# EtherNet.net
KiCad netlist of a schematic drawn in Altium Designer
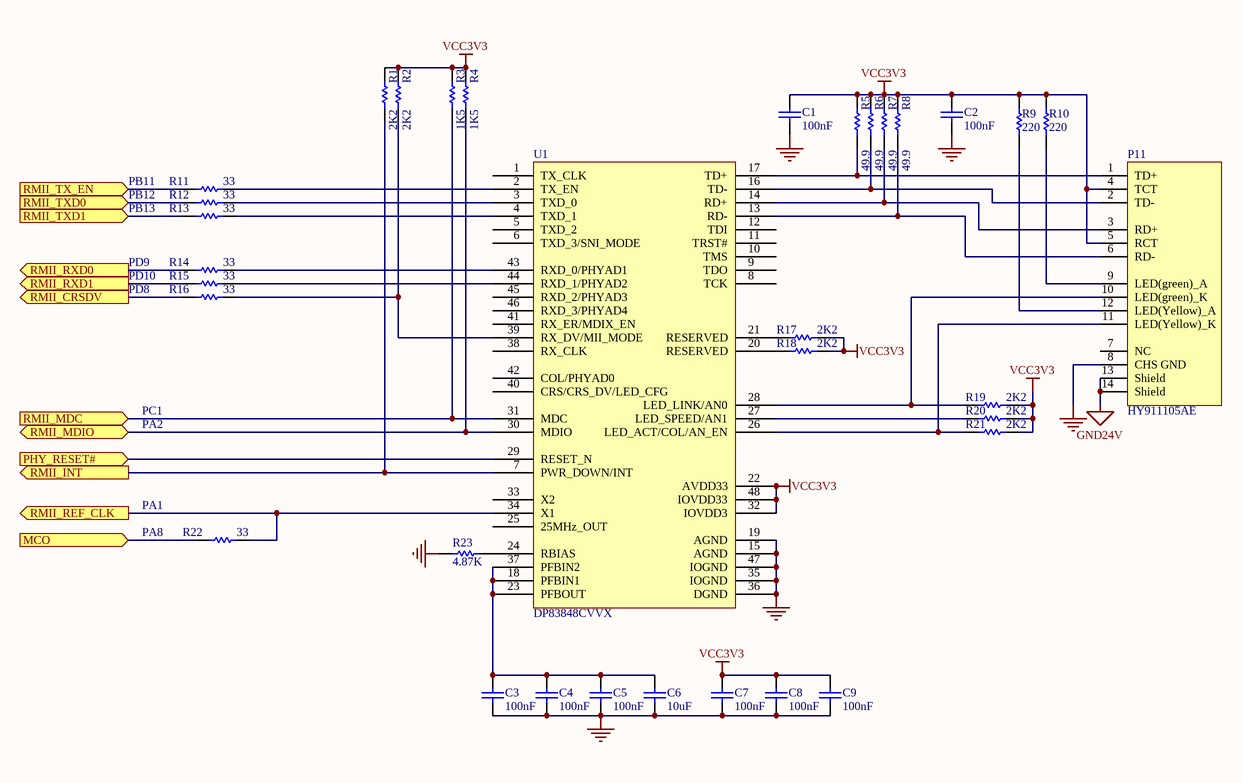
[diagram p0: EtherNet.SchDoc]

(export (version "E")
  (design (tool "Eeschema 10.0.6"))
  (components
    (comp (ref "C1")
      (value "100nF")
      (footprint "0805_C")
      (description "贴片电容")
      (libsource (lib "Miscellaneous Devices LC") (part "0805 100nF(104) 10% 50V"))
    )
    (comp (ref "C2")
      (value "100nF")
      (footprint "0805_C")
      (description "贴片电容")
      (libsource (lib "Miscellaneous Devices LC") (part "0805 100nF(104) 10% 50V"))
    )
    (comp (ref "C3")
      (value "100nF")
      (footprint "0805_C")
      (description "贴片电容")
      (libsource (lib "Miscellaneous Devices LC") (part "0805 100nF(104) 10% 50V"))
    )
    (comp (ref "C4")
      (value "100nF")
      (footprint "0805_C")
      (description "贴片电容")
      (libsource (lib "Miscellaneous Devices LC") (part "0805 100nF(104) 10% 50V"))
    )
    (comp (ref "C5")
      (value "100nF")
      (footprint "0805_C")
      (description "贴片电容")
      (libsource (lib "Miscellaneous Devices LC") (part "0805 100nF(104) 10% 50V"))
    )
    (comp (ref "C6")
      (value "10uF")
      (footprint "0805_C")
      (description "贴片电容")
      (libsource (lib "Miscellaneous Devices LC") (part "0805 10uF (106) 10% 25V"))
    )
    (comp (ref "C7")
      (value "100nF")
      (footprint "0805_C")
      (description "贴片电容")
      (libsource (lib "Miscellaneous Devices LC") (part "0805 100nF(104) 10% 50V"))
    )
    (comp (ref "C8")
      (value "100nF")
      (footprint "0805_C")
      (description "贴片电容")
      (libsource (lib "Miscellaneous Devices LC") (part "0805 100nF(104) 10% 50V"))
    )
    (comp (ref "C9")
      (value "100nF")
      (footprint "0805_C")
      (description "贴片电容")
      (libsource (lib "Miscellaneous Devices LC") (part "0805 100nF(104) 10% 50V"))
    )
    (comp (ref "P11")
      (value "HY911105AE")
      (footprint "HANRUN-A8")
      (libsource (lib "MB784") (part "J0011D21B"))
    )
    (comp (ref "R1")
      (value "2K2")
      (footprint "0805_R")
      (description "Resistor")
      (fields (field (name "PUBLISHER") "Altium Limited"))
      (libsource (lib "Miscellaneous Devices") (part "Res1"))
    )
    (comp (ref "R2")
      (value "2K2")
      (footprint "0805_R")
      (description "Resistor")
      (fields (field (name "PUBLISHER") "Altium Limited"))
      (libsource (lib "Miscellaneous Devices") (part "Res1"))
    )
    (comp (ref "R3")
      (value "1K5")
      (footprint "0805_R")
      (description "Resistor")
      (fields (field (name "PUBLISHER") "Altium Limited"))
      (libsource (lib "Miscellaneous Devices") (part "Res1"))
    )
    (comp (ref "R4")
      (value "1K5")
      (footprint "0805_R")
      (description "Resistor")
      (fields (field (name "PUBLISHER") "Altium Limited"))
      (libsource (lib "Miscellaneous Devices") (part "Res1"))
    )
    (comp (ref "R5")
      (value "49.9")
      (footprint "0805_R")
      (description "Resistor")
      (fields (field (name "PUBLISHER") "Altium Limited"))
      (libsource (lib "Miscellaneous Devices") (part "Res1"))
    )
    (comp (ref "R6")
      (value "49.9")
      (footprint "0805_R")
      (description "Resistor")
      (fields (field (name "PUBLISHER") "Altium Limited"))
      (libsource (lib "Miscellaneous Devices") (part "Res1"))
    )
    (comp (ref "R7")
      (value "49.9")
      (footprint "0805_R")
      (description "Resistor")
      (fields (field (name "PUBLISHER") "Altium Limited"))
      (libsource (lib "Miscellaneous Devices") (part "Res1"))
    )
    (comp (ref "R8")
      (value "49.9")
      (footprint "0805_R")
      (description "Resistor")
      (fields (field (name "PUBLISHER") "Altium Limited"))
      (libsource (lib "Miscellaneous Devices") (part "Res1"))
    )
    (comp (ref "R9")
      (value "220")
      (footprint "0805_R")
      (description "Resistor")
      (fields (field (name "PUBLISHER") "Altium Limited"))
      (libsource (lib "Miscellaneous Devices") (part "Res1"))
    )
    (comp (ref "R10")
      (value "220")
      (footprint "0805_R")
      (description "Resistor")
      (fields (field (name "PUBLISHER") "Altium Limited"))
      (libsource (lib "Miscellaneous Devices") (part "Res1"))
    )
    (comp (ref "R11")
      (value "33")
      (footprint "0805_R")
      (description "Resistor")
      (fields (field (name "PUBLISHER") "Altium Limited"))
      (libsource (lib "Miscellaneous Devices") (part "Res1"))
    )
    (comp (ref "R12")
      (value "33")
      (footprint "0805_R")
      (description "Resistor")
      (fields (field (name "PUBLISHER") "Altium Limited"))
      (libsource (lib "Miscellaneous Devices") (part "Res1"))
    )
    (comp (ref "R13")
      (value "33")
      (footprint "0805_R")
      (description "Resistor")
      (fields (field (name "PUBLISHER") "Altium Limited"))
      (libsource (lib "Miscellaneous Devices") (part "Res1"))
    )
    (comp (ref "R14")
      (value "33")
      (footprint "0805_R")
      (description "Resistor")
      (fields (field (name "PUBLISHER") "Altium Limited"))
      (libsource (lib "Miscellaneous Devices") (part "Res1"))
    )
    (comp (ref "R15")
      (value "33")
      (footprint "0805_R")
      (description "Resistor")
      (fields (field (name "PUBLISHER") "Altium Limited"))
      (libsource (lib "Miscellaneous Devices") (part "Res1"))
    )
    (comp (ref "R16")
      (value "33")
      (footprint "0805_R")
      (description "Resistor")
      (fields (field (name "PUBLISHER") "Altium Limited"))
      (libsource (lib "Miscellaneous Devices") (part "Res1"))
    )
    (comp (ref "R17")
      (value "2K2")
      (footprint "0805_R")
      (description "Resistor")
      (fields (field (name "PUBLISHER") "Altium Limited"))
      (libsource (lib "Miscellaneous Devices") (part "Res1"))
    )
    (comp (ref "R18")
      (value "2K2")
      (footprint "0805_R")
      (description "Resistor")
      (fields (field (name "PUBLISHER") "Altium Limited"))
      (libsource (lib "Miscellaneous Devices") (part "Res1"))
    )
    (comp (ref "R19")
      (value "2K2")
      (footprint "0805_R")
      (description "Resistor")
      (fields (field (name "PUBLISHER") "Altium Limited"))
      (libsource (lib "Miscellaneous Devices") (part "Res1"))
    )
    (comp (ref "R20")
      (value "2K2")
      (footprint "0805_R")
      (description "Resistor")
      (fields (field (name "PUBLISHER") "Altium Limited"))
      (libsource (lib "Miscellaneous Devices") (part "Res1"))
    )
    (comp (ref "R21")
      (value "2K2")
      (footprint "0805_R")
      (description "Resistor")
      (fields (field (name "PUBLISHER") "Altium Limited"))
      (libsource (lib "Miscellaneous Devices") (part "Res1"))
    )
    (comp (ref "R22")
      (value "33")
      (footprint "0805_R")
      (description "Resistor")
      (fields (field (name "PUBLISHER") "Altium Limited"))
      (libsource (lib "Miscellaneous Devices") (part "Res1"))
    )
    (comp (ref "R23")
      (value "4.87K")
      (footprint "0805_R")
      (description "Resistor")
      (fields (field (name "PUBLISHER") "Altium Limited"))
      (libsource (lib "Miscellaneous Devices") (part "Res1"))
    )
    (comp (ref "U1")
      (value "DP83848CVVX")
      (footprint "LQFP-48_7x7x05P")
      (description "接口芯片")
      (libsource (lib "Miscellaneous Devices LC") (part "DP83848CVVX_[C16688]"))
    )
  )
  (nets
    (net (code "1") (name "/MCO") (class "Default")
      (node (ref "R22") (pin "2") (pinfunction "2_2") (pintype "passive"))
    )
    (net (code "2") (name "/PHY_RESET#") (class "Default")
      (node (ref "U1") (pin "29") (pinfunction "RESET_N_29") (pintype "passive"))
    )
    (net (code "3") (name "/RMII_CRSDV") (class "Default")
      (node (ref "R16") (pin "2") (pinfunction "2_2") (pintype "passive"))
    )
    (net (code "4") (name "/RMII_INT") (class "Default")
      (node (ref "R1") (pin "1") (pinfunction "1_1") (pintype "passive"))
      (node (ref "U1") (pin "7") (pinfunction "PWR_DOWN/INT_7") (pintype "passive"))
    )
    (net (code "5") (name "/RMII_MDC") (class "Default")
      (node (ref "R3") (pin "1") (pinfunction "1_1") (pintype "passive"))
      (node (ref "U1") (pin "31") (pinfunction "MDC_31") (pintype "passive"))
    )
    (net (code "6") (name "/RMII_MDIO") (class "Default")
      (node (ref "R4") (pin "1") (pinfunction "1_1") (pintype "passive"))
      (node (ref "U1") (pin "30") (pinfunction "MDIO_30") (pintype "passive"))
    )
    (net (code "7") (name "/RMII_REF_CLK") (class "Default")
      (node (ref "R22") (pin "1") (pinfunction "1_1") (pintype "passive"))
      (node (ref "U1") (pin "34") (pinfunction "X1_34") (pintype "passive"))
    )
    (net (code "8") (name "/RMII_RXD0") (class "Default")
      (node (ref "R14") (pin "2") (pinfunction "2_2") (pintype "passive"))
    )
    (net (code "9") (name "/RMII_RXD1") (class "Default")
      (node (ref "R15") (pin "2") (pinfunction "2_2") (pintype "passive"))
    )
    (net (code "10") (name "/RMII_TXD0") (class "Default")
      (node (ref "R12") (pin "2") (pinfunction "2_2") (pintype "passive"))
    )
    (net (code "11") (name "/RMII_TXD1") (class "Default")
      (node (ref "R13") (pin "2") (pinfunction "2_2") (pintype "passive"))
    )
    (net (code "12") (name "/RMII_TX_EN") (class "Default")
      (node (ref "R11") (pin "2") (pinfunction "2_2") (pintype "passive"))
    )
    (net (code "13") (name "GND") (class "Default")
      (node (ref "C1") (pin "2") (pinfunction "2_2") (pintype "passive"))
      (node (ref "C2") (pin "2") (pinfunction "2_2") (pintype "passive"))
      (node (ref "C3") (pin "2") (pinfunction "2_2") (pintype "passive"))
      (node (ref "C4") (pin "2") (pinfunction "2_2") (pintype "passive"))
      (node (ref "C5") (pin "2") (pinfunction "2_2") (pintype "passive"))
      (node (ref "C6") (pin "1") (pinfunction "1_1") (pintype "passive"))
      (node (ref "C7") (pin "2") (pinfunction "2_2") (pintype "passive"))
      (node (ref "C8") (pin "2") (pinfunction "2_2") (pintype "passive"))
      (node (ref "C9") (pin "2") (pinfunction "2_2") (pintype "passive"))
      (node (ref "P11") (pin "8") (pinfunction "CHS_GND_8") (pintype "passive"))
      (node (ref "R23") (pin "1") (pinfunction "1_1") (pintype "passive"))
      (node (ref "U1") (pin "15") (pinfunction "AGND_15") (pintype "passive"))
      (node (ref "U1") (pin "19") (pinfunction "AGND_19") (pintype "passive"))
      (node (ref "U1") (pin "35") (pinfunction "IOGND_35") (pintype "passive"))
      (node (ref "U1") (pin "36") (pinfunction "DGND_36") (pintype "passive"))
      (node (ref "U1") (pin "47") (pinfunction "IOGND_47") (pintype "passive"))
    )
    (net (code "14") (name "GND24V") (class "Default")
      (node (ref "P11") (pin "13") (pinfunction "Shield_13") (pintype "passive"))
      (node (ref "P11") (pin "14") (pinfunction "Shield_14") (pintype "passive"))
    )
    (net (code "15") (name "Net-(P11-LED(Yellow)_A)") (class "Default")
      (node (ref "P11") (pin "12") (pinfunction "LED(Yellow)_A_12") (pintype "passive"))
      (node (ref "R9") (pin "1") (pinfunction "1_1") (pintype "passive"))
    )
    (net (code "16") (name "Net-(P11-LED(Yellow)_K)") (class "Default")
      (node (ref "P11") (pin "11") (pinfunction "LED(Yellow)_K_11") (pintype "passive"))
      (node (ref "R21") (pin "1") (pinfunction "1_1") (pintype "passive"))
      (node (ref "U1") (pin "26") (pinfunction "LED_ACT/COL/AN_EN_26") (pintype "passive"))
    )
    (net (code "17") (name "Net-(P11-LED(green)_A)") (class "Default")
      (node (ref "P11") (pin "9") (pinfunction "LED(green)_A_9") (pintype "passive"))
      (node (ref "R10") (pin "1") (pinfunction "1_1") (pintype "passive"))
    )
    (net (code "18") (name "Net-(P11-LED(green)_K)") (class "Default")
      (node (ref "P11") (pin "10") (pinfunction "LED(green)_K_10") (pintype "passive"))
      (node (ref "R19") (pin "1") (pinfunction "1_1") (pintype "passive"))
      (node (ref "U1") (pin "28") (pinfunction "LED_LINK/AN0_28") (pintype "passive"))
    )
    (net (code "19") (name "Net-(P11-RD+)") (class "Default")
      (node (ref "P11") (pin "3") (pinfunction "RD+_3") (pintype "passive"))
      (node (ref "R7") (pin "1") (pinfunction "1_1") (pintype "passive"))
      (node (ref "U1") (pin "14") (pinfunction "RD+_14") (pintype "passive"))
    )
    (net (code "20") (name "Net-(P11-RD-)") (class "Default")
      (node (ref "P11") (pin "6") (pinfunction "RD-_6") (pintype "passive"))
      (node (ref "R8") (pin "1") (pinfunction "1_1") (pintype "passive"))
      (node (ref "U1") (pin "13") (pinfunction "RD-_13") (pintype "passive"))
    )
    (net (code "21") (name "Net-(P11-TD+)") (class "Default")
      (node (ref "P11") (pin "1") (pinfunction "TD+_1") (pintype "passive"))
      (node (ref "R5") (pin "1") (pinfunction "1_1") (pintype "passive"))
      (node (ref "U1") (pin "17") (pinfunction "TD+_17") (pintype "passive"))
    )
    (net (code "22") (name "Net-(P11-TD-)") (class "Default")
      (node (ref "P11") (pin "2") (pinfunction "TD-_2") (pintype "passive"))
      (node (ref "R6") (pin "1") (pinfunction "1_1") (pintype "passive"))
      (node (ref "U1") (pin "16") (pinfunction "TD-_16") (pintype "passive"))
    )
    (net (code "23") (name "Net-(R17-Pad1)") (class "Default")
      (node (ref "R17") (pin "1") (pinfunction "1_1") (pintype "passive"))
      (node (ref "U1") (pin "21") (pinfunction "RESERVED_21") (pintype "passive"))
    )
    (net (code "24") (name "Net-(R18-Pad1)") (class "Default")
      (node (ref "R18") (pin "1") (pinfunction "1_1") (pintype "passive"))
      (node (ref "U1") (pin "20") (pinfunction "RESERVED_20") (pintype "passive"))
    )
    (net (code "25") (name "Net-(U1-LED_SPEED{slash}AN1)") (class "Default")
      (node (ref "R20") (pin "1") (pinfunction "1_1") (pintype "passive"))
      (node (ref "U1") (pin "27") (pinfunction "LED_SPEED/AN1_27") (pintype "passive"))
    )
    (net (code "26") (name "Net-(U1-PFBIN1)") (class "Default")
      (node (ref "C3") (pin "1") (pinfunction "1_1") (pintype "passive"))
      (node (ref "C4") (pin "1") (pinfunction "1_1") (pintype "passive"))
      (node (ref "C5") (pin "1") (pinfunction "1_1") (pintype "passive"))
      (node (ref "C6") (pin "2") (pinfunction "2_2") (pintype "passive"))
      (node (ref "U1") (pin "18") (pinfunction "PFBIN1_18") (pintype "passive"))
      (node (ref "U1") (pin "23") (pinfunction "PFBOUT_23") (pintype "passive"))
      (node (ref "U1") (pin "37") (pinfunction "PFBIN2_37") (pintype "passive"))
    )
    (net (code "27") (name "Net-(U1-RBIAS)") (class "Default")
      (node (ref "R23") (pin "2") (pinfunction "2_2") (pintype "passive"))
      (node (ref "U1") (pin "24") (pinfunction "RBIAS_24") (pintype "passive"))
    )
    (net (code "28") (name "Net-(U1-RXD_0{slash}PHYAD1)") (class "Default")
      (node (ref "R14") (pin "1") (pinfunction "1_1") (pintype "passive"))
      (node (ref "U1") (pin "43") (pinfunction "RXD_0/PHYAD1_43") (pintype "passive"))
    )
    (net (code "29") (name "Net-(U1-RXD_1{slash}PHYAD2)") (class "Default")
      (node (ref "R15") (pin "1") (pinfunction "1_1") (pintype "passive"))
      (node (ref "U1") (pin "44") (pinfunction "RXD_1/PHYAD2_44") (pintype "passive"))
    )
    (net (code "30") (name "Net-(U1-RX_DV{slash}MII_MODE)") (class "Default")
      (node (ref "R16") (pin "1") (pinfunction "1_1") (pintype "passive"))
      (node (ref "R2") (pin "1") (pinfunction "1_1") (pintype "passive"))
      (node (ref "U1") (pin "39") (pinfunction "RX_DV/MII_MODE_39") (pintype "passive"))
    )
    (net (code "31") (name "Net-(U1-TXD_0)") (class "Default")
      (node (ref "R12") (pin "1") (pinfunction "1_1") (pintype "passive"))
      (node (ref "U1") (pin "3") (pinfunction "TXD_0_3") (pintype "passive"))
    )
    (net (code "32") (name "Net-(U1-TXD_1)") (class "Default")
      (node (ref "R13") (pin "1") (pinfunction "1_1") (pintype "passive"))
      (node (ref "U1") (pin "4") (pinfunction "TXD_1_4") (pintype "passive"))
    )
    (net (code "33") (name "Net-(U1-TX_EN)") (class "Default")
      (node (ref "R11") (pin "1") (pinfunction "1_1") (pintype "passive"))
      (node (ref "U1") (pin "2") (pinfunction "TX_EN_2") (pintype "passive"))
    )
    (net (code "34") (name "VCC3V3") (class "Default")
      (node (ref "C1") (pin "1") (pinfunction "1_1") (pintype "passive"))
      (node (ref "C2") (pin "1") (pinfunction "1_1") (pintype "passive"))
      (node (ref "C7") (pin "1") (pinfunction "1_1") (pintype "passive"))
      (node (ref "C8") (pin "1") (pinfunction "1_1") (pintype "passive"))
      (node (ref "C9") (pin "1") (pinfunction "1_1") (pintype "passive"))
      (node (ref "P11") (pin "4") (pinfunction "TCT_4") (pintype "passive"))
      (node (ref "P11") (pin "5") (pinfunction "RCT_5") (pintype "passive"))
      (node (ref "R1") (pin "2") (pinfunction "2_2") (pintype "passive"))
      (node (ref "R10") (pin "2") (pinfunction "2_2") (pintype "passive"))
      (node (ref "R17") (pin "2") (pinfunction "2_2") (pintype "passive"))
      (node (ref "R18") (pin "2") (pinfunction "2_2") (pintype "passive"))
      (node (ref "R19") (pin "2") (pinfunction "2_2") (pintype "passive"))
      (node (ref "R2") (pin "2") (pinfunction "2_2") (pintype "passive"))
      (node (ref "R20") (pin "2") (pinfunction "2_2") (pintype "passive"))
      (node (ref "R21") (pin "2") (pinfunction "2_2") (pintype "passive"))
      (node (ref "R3") (pin "2") (pinfunction "2_2") (pintype "passive"))
      (node (ref "R4") (pin "2") (pinfunction "2_2") (pintype "passive"))
      (node (ref "R5") (pin "2") (pinfunction "2_2") (pintype "passive"))
      (node (ref "R6") (pin "2") (pinfunction "2_2") (pintype "passive"))
      (node (ref "R7") (pin "2") (pinfunction "2_2") (pintype "passive"))
      (node (ref "R8") (pin "2") (pinfunction "2_2") (pintype "passive"))
      (node (ref "R9") (pin "2") (pinfunction "2_2") (pintype "passive"))
      (node (ref "U1") (pin "22") (pinfunction "AVDD33_22") (pintype "passive"))
      (node (ref "U1") (pin "32") (pinfunction "IOVDD3_32") (pintype "passive"))
      (node (ref "U1") (pin "48") (pinfunction "IOVDD33_48") (pintype "passive"))
    )
    (net (code "35") (name "unconnected-(P11-NC-Pad7)") (class "Default")
      (node (ref "P11") (pin "7") (pinfunction "NC_7") (pintype "passive"))
    )
    (net (code "36") (name "unconnected-(U1-25MHz_OUT-Pad25)") (class "Default")
      (node (ref "U1") (pin "25") (pinfunction "25MHz_OUT_25") (pintype "passive"))
    )
    (net (code "37") (name "unconnected-(U1-COL{slash}PHYAD0-Pad42)") (class "Default")
      (node (ref "U1") (pin "42") (pinfunction "COL/PHYAD0_42") (pintype "passive"))
    )
    (net (code "38") (name "unconnected-(U1-CRS{slash}CRS_DV{slash}LED_CFG-Pad40)") (class "Default")
      (node (ref "U1") (pin "40") (pinfunction "CRS/CRS_DV/LED_CFG_40") (pintype "passive"))
    )
    (net (code "39") (name "unconnected-(U1-RXD_2{slash}PHYAD3-Pad45)") (class "Default")
      (node (ref "U1") (pin "45") (pinfunction "RXD_2/PHYAD3_45") (pintype "passive"))
    )
    (net (code "40") (name "unconnected-(U1-RXD_3{slash}PHYAD4-Pad46)") (class "Default")
      (node (ref "U1") (pin "46") (pinfunction "RXD_3/PHYAD4_46") (pintype "passive"))
    )
    (net (code "41") (name "unconnected-(U1-RX_CLK-Pad38)") (class "Default")
      (node (ref "U1") (pin "38") (pinfunction "RX_CLK_38") (pintype "passive"))
    )
    (net (code "42") (name "unconnected-(U1-RX_ER{slash}MDIX_EN-Pad41)") (class "Default")
      (node (ref "U1") (pin "41") (pinfunction "RX_ER/MDIX_EN_41") (pintype "passive"))
    )
    (net (code "43") (name "unconnected-(U1-TCK-Pad8)") (class "Default")
      (node (ref "U1") (pin "8") (pinfunction "TCK_8") (pintype "passive"))
    )
    (net (code "44") (name "unconnected-(U1-TDI-Pad12)") (class "Default")
      (node (ref "U1") (pin "12") (pinfunction "TDI_12") (pintype "passive"))
    )
    (net (code "45") (name "unconnected-(U1-TDO-Pad9)") (class "Default")
      (node (ref "U1") (pin "9") (pinfunction "TDO_9") (pintype "passive"))
    )
    (net (code "46") (name "unconnected-(U1-TMS-Pad10)") (class "Default")
      (node (ref "U1") (pin "10") (pinfunction "TMS_10") (pintype "passive"))
    )
    (net (code "47") (name "unconnected-(U1-TRST#-Pad11)") (class "Default")
      (node (ref "U1") (pin "11") (pinfunction "TRST#_11") (pintype "passive"))
    )
    (net (code "48") (name "unconnected-(U1-TXD_2-Pad5)") (class "Default")
      (node (ref "U1") (pin "5") (pinfunction "TXD_2_5") (pintype "passive"))
    )
    (net (code "49") (name "unconnected-(U1-TXD_3{slash}SNI_MODE-Pad6)") (class "Default")
      (node (ref "U1") (pin "6") (pinfunction "TXD_3/SNI_MODE_6") (pintype "passive"))
    )
    (net (code "50") (name "unconnected-(U1-TX_CLK-Pad1)") (class "Default")
      (node (ref "U1") (pin "1") (pinfunction "TX_CLK_1") (pintype "passive"))
    )
    (net (code "51") (name "unconnected-(U1-X2-Pad33)") (class "Default")
      (node (ref "U1") (pin "33") (pinfunction "X2_33") (pintype "passive"))
    )
  )
)
